# Part20_UART_BLE.net
KiCad netlist of a schematic drawn in Altium Designer
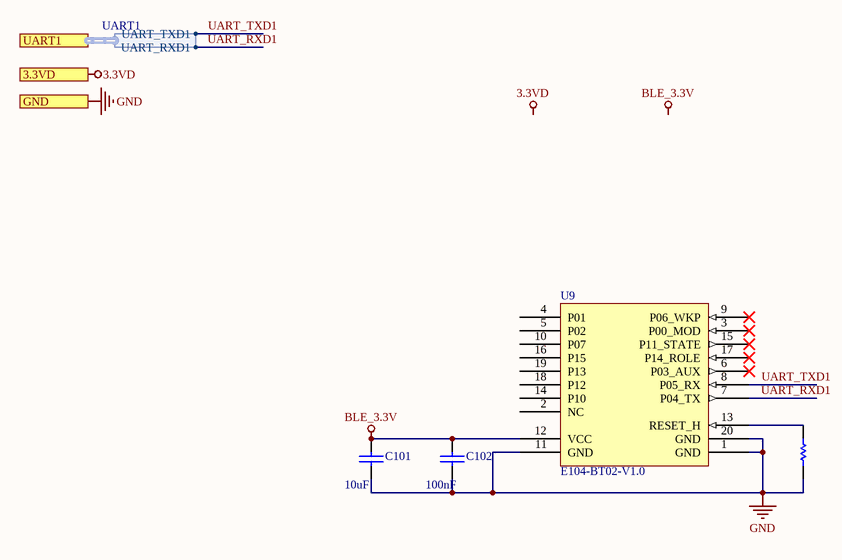
[diagram p0: Part20_UART_BLE.SchDoc]

(export (version "E")
  (design (tool "Eeschema 10.0.6"))
  (components
    (comp (ref "C101")
      (value "10uF")
      (footprint "0603C")
      (description "无极性电容")
      (libsource (lib "电容") (part "CAP"))
    )
    (comp (ref "C102")
      (value "100nF")
      (footprint "0603C")
      (description "无极性电容")
      (libsource (lib "电容") (part "CAP"))
    )
    (comp (ref "R82") (value "470R") (footprint "0402R") (libsource (lib "电阻") (part "RES")))
    (comp (ref "U9")
      (value "E104-BT02-V1.0")
      (footprint "PE104-BT02")
      (libsource (lib "MT7688_Lib") (part "E104-BT02-V1.0"))
    )
  )
  (nets
    (net (code "2") (name "/UART_RXD1") (class "Default")
      (node (ref "U9") (pin "7") (pinfunction "P04_TX_7") (pintype "output"))
    )
    (net (code "3") (name "/UART_TXD1") (class "Default")
      (node (ref "U9") (pin "8") (pinfunction "P05_RX_8") (pintype "input"))
    )
    (net (code "6") (name "BLE_3.3V") (class "Default")
      (node (ref "C101") (pin "2") (pinfunction "2_2") (pintype "passive"))
      (node (ref "C102") (pin "2") (pinfunction "2_2") (pintype "passive"))
      (node (ref "U9") (pin "12") (pinfunction "VCC_12") (pintype "power_in"))
    )
    (net (code "7") (name "GND") (class "Default")
      (node (ref "C101") (pin "1") (pinfunction "1_1") (pintype "passive"))
      (node (ref "C102") (pin "1") (pinfunction "1_1") (pintype "passive"))
      (node (ref "R82") (pin "1") (pinfunction "1_1") (pintype "passive"))
      (node (ref "U9") (pin "1") (pinfunction "GND_1") (pintype "power_in"))
      (node (ref "U9") (pin "11") (pinfunction "GND_11") (pintype "power_in"))
      (node (ref "U9") (pin "20") (pinfunction "GND_20") (pintype "power_in"))
    )
    (net (code "8") (name "Net-(U9-RESET_H)") (class "Default")
      (node (ref "R82") (pin "2") (pinfunction "2_2") (pintype "passive"))
      (node (ref "U9") (pin "13") (pinfunction "RESET_H_13") (pintype "input"))
    )
    (net (code "9") (name "unconnected-(U9-NC-Pad2)") (class "Default")
      (node (ref "U9") (pin "2") (pinfunction "NC_2") (pintype "passive"))
    )
    (net (code "10") (name "unconnected-(U9-P00_MOD-Pad3)") (class "Default")
      (node (ref "U9") (pin "3") (pinfunction "P00_MOD_3") (pintype "input+no_connect"))
    )
    (net (code "11") (name "unconnected-(U9-P01-Pad4)") (class "Default")
      (node (ref "U9") (pin "4") (pinfunction "P01_4") (pintype "passive"))
    )
    (net (code "12") (name "unconnected-(U9-P02-Pad5)") (class "Default")
      (node (ref "U9") (pin "5") (pinfunction "P02_5") (pintype "passive"))
    )
    (net (code "13") (name "unconnected-(U9-P03_AUX-Pad6)") (class "Default")
      (node (ref "U9") (pin "6") (pinfunction "P03_AUX_6") (pintype "output+no_connect"))
    )
    (net (code "14") (name "unconnected-(U9-P06_WKP-Pad9)") (class "Default")
      (node (ref "U9") (pin "9") (pinfunction "P06_WKP_9") (pintype "input+no_connect"))
    )
    (net (code "15") (name "unconnected-(U9-P07-Pad10)") (class "Default")
      (node (ref "U9") (pin "10") (pinfunction "P07_10") (pintype "passive"))
    )
    (net (code "16") (name "unconnected-(U9-P10-Pad14)") (class "Default")
      (node (ref "U9") (pin "14") (pinfunction "P10_14") (pintype "passive"))
    )
    (net (code "17") (name "unconnected-(U9-P11_STATE-Pad15)") (class "Default")
      (node (ref "U9") (pin "15") (pinfunction "P11_STATE_15") (pintype "output+no_connect"))
    )
    (net (code "18") (name "unconnected-(U9-P12-Pad18)") (class "Default")
      (node (ref "U9") (pin "18") (pinfunction "P12_18") (pintype "passive"))
    )
    (net (code "19") (name "unconnected-(U9-P13-Pad19)") (class "Default")
      (node (ref "U9") (pin "19") (pinfunction "P13_19") (pintype "passive"))
    )
    (net (code "20") (name "unconnected-(U9-P14_ROLE-Pad17)") (class "Default")
      (node (ref "U9") (pin "17") (pinfunction "P14_ROLE_17") (pintype "input+no_connect"))
    )
    (net (code "21") (name "unconnected-(U9-P15-Pad16)") (class "Default")
      (node (ref "U9") (pin "16") (pinfunction "P15_16") (pintype "passive"))
    )
  )
)
